# RS232.net
KiCad netlist of a schematic drawn in Altium Designer
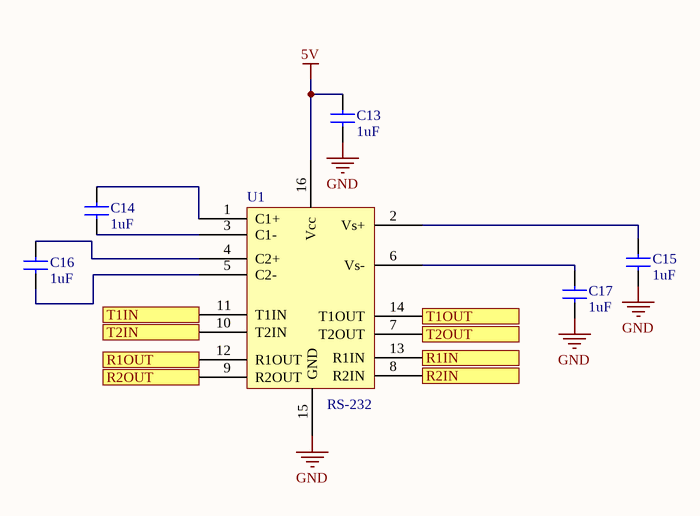
[diagram p0: RS232.SchDoc]

(export (version "E")
  (design (tool "Eeschema 10.0.6"))
  (components
    (comp (ref "C13")
      (value "1uF")
      (footprint "CAPC0603")
      (fields (field (name "Comment") "Cap"))
      (libsource (lib "SubjuGator8") (part "Cap"))
    )
    (comp (ref "C14")
      (value "1uF")
      (footprint "CAPC0603")
      (fields (field (name "Comment") "Cap"))
      (libsource (lib "SubjuGator8") (part "Cap"))
    )
    (comp (ref "C15")
      (value "1uF")
      (footprint "CAPC0603")
      (fields (field (name "Comment") "Cap"))
      (libsource (lib "SubjuGator8") (part "Cap"))
    )
    (comp (ref "C16")
      (value "1uF")
      (footprint "CAPC0603")
      (fields (field (name "Comment") "Cap"))
      (libsource (lib "SubjuGator8") (part "Cap"))
    )
    (comp (ref "C17")
      (value "1uF")
      (footprint "CAPC0603")
      (fields (field (name "Comment") "Cap"))
      (libsource (lib "SubjuGator8") (part "Cap"))
    )
    (comp (ref "U1")
      (value "RS-232")
      (footprint "RS-232")
      (description "IC DVR/RCVR RS232 DUAL 16SOIC")
      (libsource (lib "SubjuGator8") (part "RS-232"))
    )
  )
  (nets
    (net (code "1") (name "/R1IN") (class "Default")
      (node (ref "U1") (pin "13") (pinfunction "R1IN_13") (pintype "passive"))
    )
    (net (code "2") (name "/R1OUT") (class "Default")
      (node (ref "U1") (pin "12") (pinfunction "R1OUT_12") (pintype "passive"))
    )
    (net (code "3") (name "/R2IN") (class "Default")
      (node (ref "U1") (pin "8") (pinfunction "R2IN_8") (pintype "passive"))
    )
    (net (code "4") (name "/R2OUT") (class "Default")
      (node (ref "U1") (pin "9") (pinfunction "R2OUT_9") (pintype "passive"))
    )
    (net (code "5") (name "/T1IN") (class "Default")
      (node (ref "U1") (pin "11") (pinfunction "T1IN_11") (pintype "passive"))
    )
    (net (code "6") (name "/T1OUT") (class "Default")
      (node (ref "U1") (pin "14") (pinfunction "T1OUT_14") (pintype "passive"))
    )
    (net (code "7") (name "/T2IN") (class "Default")
      (node (ref "U1") (pin "10") (pinfunction "T2IN_10") (pintype "passive"))
    )
    (net (code "8") (name "/T2OUT") (class "Default")
      (node (ref "U1") (pin "7") (pinfunction "T2OUT_7") (pintype "passive"))
    )
    (net (code "9") (name "5V") (class "Default")
      (node (ref "C13") (pin "1") (pinfunction "A_1") (pintype "passive"))
      (node (ref "U1") (pin "16") (pinfunction "Vcc_16") (pintype "passive"))
    )
    (net (code "10") (name "GND") (class "Default")
      (node (ref "C13") (pin "2") (pinfunction "B_2") (pintype "passive"))
      (node (ref "C15") (pin "2") (pinfunction "B_2") (pintype "passive"))
      (node (ref "C17") (pin "2") (pinfunction "B_2") (pintype "passive"))
      (node (ref "U1") (pin "15") (pinfunction "GND_15") (pintype "passive"))
    )
    (net (code "11") (name "Net-(C14-A)") (class "Default")
      (node (ref "C14") (pin "1") (pinfunction "A_1") (pintype "passive"))
      (node (ref "U1") (pin "1") (pinfunction "C1+_1") (pintype "passive"))
    )
    (net (code "12") (name "Net-(C14-B)") (class "Default")
      (node (ref "C14") (pin "2") (pinfunction "B_2") (pintype "passive"))
      (node (ref "U1") (pin "3") (pinfunction "C1-_3") (pintype "passive"))
    )
    (net (code "13") (name "Net-(C15-A)") (class "Default")
      (node (ref "C15") (pin "1") (pinfunction "A_1") (pintype "passive"))
      (node (ref "U1") (pin "2") (pinfunction "Vs+_2") (pintype "passive"))
    )
    (net (code "14") (name "Net-(C16-A)") (class "Default")
      (node (ref "C16") (pin "1") (pinfunction "A_1") (pintype "passive"))
      (node (ref "U1") (pin "4") (pinfunction "C2+_4") (pintype "passive"))
    )
    (net (code "15") (name "Net-(C16-B)") (class "Default")
      (node (ref "C16") (pin "2") (pinfunction "B_2") (pintype "passive"))
      (node (ref "U1") (pin "5") (pinfunction "C2-_5") (pintype "passive"))
    )
    (net (code "16") (name "Net-(C17-A)") (class "Default")
      (node (ref "C17") (pin "1") (pinfunction "A_1") (pintype "passive"))
      (node (ref "U1") (pin "6") (pinfunction "Vs-_6") (pintype "passive"))
    )
  )
)
